# motor_driver_2.net
KiCad netlist of a schematic drawn in Altium Designer
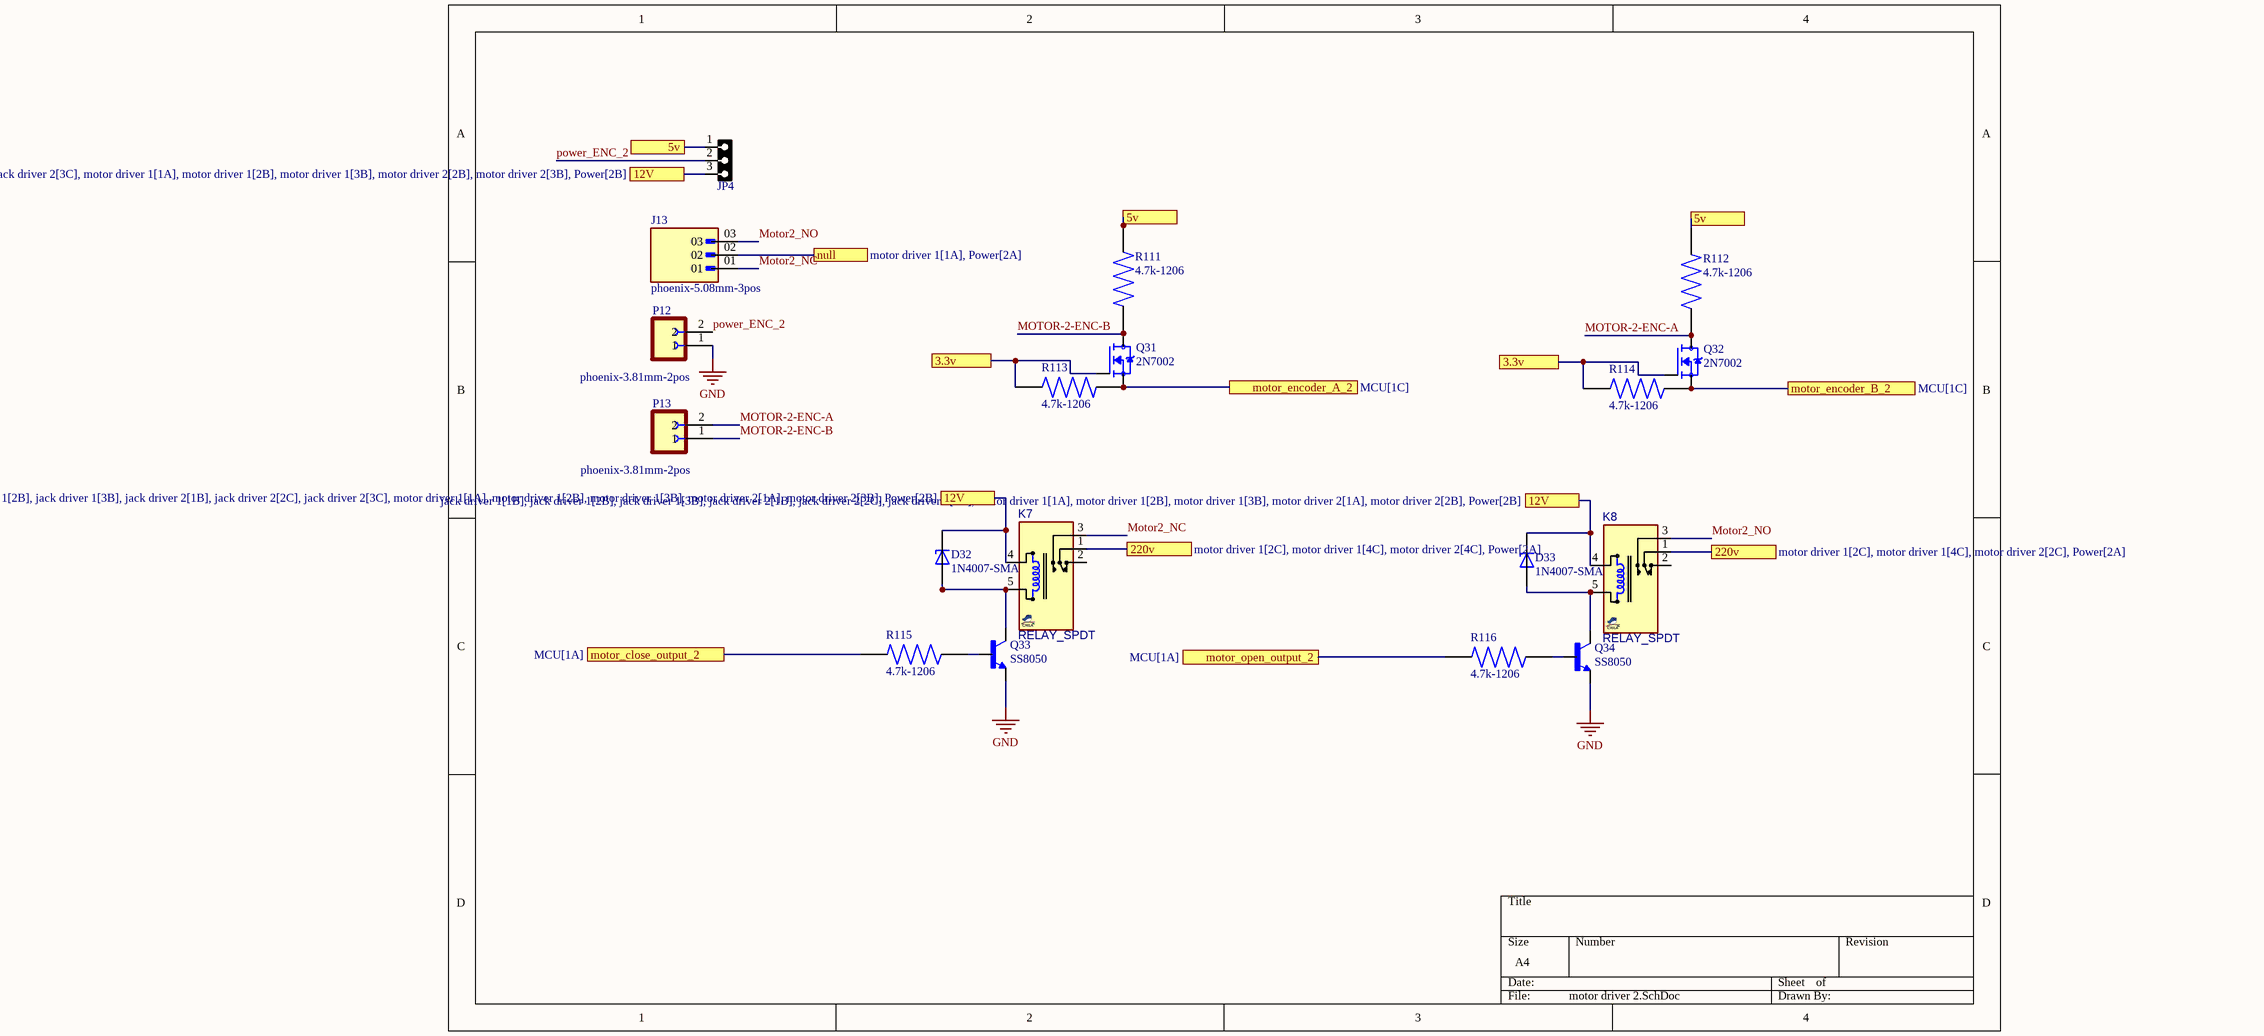
[diagram p0: motor driver 2.SchDoc]

(export (version "E")
  (design (tool "Eeschema 10.0.6"))
  (components
    (comp (ref "D32")
      (value "1N4007-SMA")
      (footprint "DIOM4325X250N")
      (description "400W, 30.4V, 5%, Unidirectional, TVS")
      (fields (field (name "MF") "Taiwan Semiconductor") (field (name "MP") "SMAJ26A"))
      (libsource (lib "diode-sma") (part "SMAJ26A"))
    )
    (comp (ref "D33")
      (value "1N4007-SMA")
      (footprint "DIOM4325X250N")
      (description "400W, 30.4V, 5%, Unidirectional, TVS")
      (fields (field (name "MF") "Taiwan Semiconductor") (field (name "MP") "SMAJ26A"))
      (libsource (lib "diode-sma") (part "SMAJ26A"))
    )
    (comp (ref "J13")
      (value "phoenix-5.08mm-3pos")
      (footprint "PHOENIX_1759020")
      (description "Pluggable Header 5.08mm 12AWG 320V 12A 3 Position COMBICON MSTB Series ¦ Phoenix Contact 1759020")
      (fields (field (name "MF") "Phoenix Contact") (field (name "MP") "1759020"))
      (libsource (lib "phoenix-3pos") (part "1759020"))
    )
    (comp (ref "JP4")
      (value "HDRF3")
      (footprint "HDRLP_F_1X3")
      (description "CONN, HEADER, Male, pitch: 2.54mm, 3POS")
      (libsource (lib "conn_2.54mm_lp") (part "HDRLP_F_1X3"))
    )
    (comp (ref "K7")
      (value "RELAY_SPDT")
      (footprint "REL_SPDT_5_1512")
      (description "Relay, SPDT, 5P, 15.4X12.1mm, 16V/30A")
      (fields (field (name "MANF") "OMRON") (field (name "MANF_P#") "G8QN-1C4 DC12"))
      (libsource (lib "relay") (part "RELAY_SPDT_5_1512_G8QN"))
    )
    (comp (ref "K8")
      (value "RELAY_SPDT")
      (footprint "REL_SPDT_5_1512")
      (description "Relay, SPDT, 5P, 15.4X12.1mm, 16V/30A")
      (fields (field (name "MANF") "OMRON") (field (name "MANF_P#") "G8QN-1C4 DC12"))
      (libsource (lib "relay") (part "RELAY_SPDT_5_1512_G8QN"))
    )
    (comp (ref "P12")
      (value "phoenix-3.81mm-2pos")
      (footprint "PHOENIX_1803578")
      (description "2 Position Terminal Block Plug, Female Sockets 0.150 (3.81mm) 180Â° Free Hanging (In-Line)")
      (fields (field (name "MF") "Phoenix Contact") (field (name "MP") "1803578"))
      (libsource (lib "terminal-phoenix-3.81mm-2pos") (part "1803578"))
    )
    (comp (ref "P13")
      (value "phoenix-3.81mm-2pos")
      (footprint "PHOENIX_1803578")
      (description "2 Position Terminal Block Plug, Female Sockets 0.150 (3.81mm) 180Â° Free Hanging (In-Line)")
      (fields (field (name "MF") "Phoenix Contact") (field (name "MP") "1803578"))
      (libsource (lib "terminal-phoenix-3.81mm-2pos") (part "1803578"))
    )
    (comp (ref "Q31")
      (value "2N7002")
      (footprint "SOT95P240X111-3N")
      (description "N-Channel 60V 280mA (Ta) 350mW (Ta) Surface Mount SOT-23-3 (TO-236)")
      (fields (field (name "MF") "{'manufacturer': u'onsemi'}"))
      (libsource (lib "2N7002-SOT23") (part "2N7002"))
    )
    (comp (ref "Q32")
      (value "2N7002")
      (footprint "SOT95P240X111-3N")
      (description "N-Channel 60V 280mA (Ta) 350mW (Ta) Surface Mount SOT-23-3 (TO-236)")
      (fields (field (name "MF") "{'manufacturer': u'onsemi'}"))
      (libsource (lib "2N7002-SOT23") (part "2N7002"))
    )
    (comp (ref "Q33")
      (value "SS8050")
      (footprint "TRANS_SS8050-G")
      (description "Bipolar (BJT) Transistor NPN 25 V 1.5 A 100MHz 300 mW Surface Mount SOT-23-3")
      (fields (field (name "DIGI-KEY_PART_NUMBER") "641-1790-2-ND") (field (name "MP") "SS8050G"))
      (libsource (lib "SS8050-G") (part "SS8050-G"))
    )
    (comp (ref "Q34")
      (value "SS8050")
      (footprint "TRANS_SS8050-G")
      (description "Bipolar (BJT) Transistor NPN 25 V 1.5 A 100MHz 300 mW Surface Mount SOT-23-3")
      (fields (field (name "DIGI-KEY_PART_NUMBER") "641-1790-2-ND") (field (name "MP") "SS8050G"))
      (libsource (lib "SS8050-G") (part "SS8050-G"))
    )
    (comp (ref "R111")
      (value "4.7k-1206")
      (footprint "RESC3015X65N")
      (description "Res Thin Film 1206 10K Ohm 0.1% 1/8W Â±25ppm/Â°C Molded SMD SMD Paper T/R")
      (fields (field (name "MF") "TE Connectivity") (field (name "MP") "CPF1206B10KE1"))
      (libsource (lib "resistor-1206") (part "CPF1206B10KE1"))
    )
    (comp (ref "R112")
      (value "4.7k-1206")
      (footprint "RESC3015X65N")
      (description "Res Thin Film 1206 10K Ohm 0.1% 1/8W Â±25ppm/Â°C Molded SMD SMD Paper T/R")
      (fields (field (name "MF") "TE Connectivity") (field (name "MP") "CPF1206B10KE1"))
      (libsource (lib "resistor-1206") (part "CPF1206B10KE1"))
    )
    (comp (ref "R113")
      (value "4.7k-1206")
      (footprint "RESC3015X65N")
      (description "Res Thin Film 1206 10K Ohm 0.1% 1/8W Â±25ppm/Â°C Molded SMD SMD Paper T/R")
      (fields (field (name "MF") "TE Connectivity") (field (name "MP") "CPF1206B10KE1"))
      (libsource (lib "resistor-1206") (part "CPF1206B10KE1"))
    )
    (comp (ref "R114")
      (value "4.7k-1206")
      (footprint "RESC3015X65N")
      (description "Res Thin Film 1206 10K Ohm 0.1% 1/8W Â±25ppm/Â°C Molded SMD SMD Paper T/R")
      (fields (field (name "MF") "TE Connectivity") (field (name "MP") "CPF1206B10KE1"))
      (libsource (lib "resistor-1206") (part "CPF1206B10KE1"))
    )
    (comp (ref "R115")
      (value "4.7k-1206")
      (footprint "RESC3015X65N")
      (description "Res Thin Film 1206 10K Ohm 0.1% 1/8W Â±25ppm/Â°C Molded SMD SMD Paper T/R")
      (fields (field (name "MF") "TE Connectivity") (field (name "MP") "CPF1206B10KE1"))
      (libsource (lib "resistor-1206") (part "CPF1206B10KE1"))
    )
    (comp (ref "R116")
      (value "4.7k-1206")
      (footprint "RESC3015X65N")
      (description "Res Thin Film 1206 10K Ohm 0.1% 1/8W Â±25ppm/Â°C Molded SMD SMD Paper T/R")
      (fields (field (name "MF") "TE Connectivity") (field (name "MP") "CPF1206B10KE1"))
      (libsource (lib "resistor-1206") (part "CPF1206B10KE1"))
    )
  )
  (nets
    (net (code "1") (name "/3.3v") (class "Default")
      (node (ref "Q31") (pin "1") (pinfunction "G_1") (pintype "passive"))
      (node (ref "Q32") (pin "1") (pinfunction "G_1") (pintype "passive"))
      (node (ref "R113") (pin "2") (pinfunction "2_2") (pintype "passive"))
      (node (ref "R114") (pin "2") (pinfunction "2_2") (pintype "passive"))
    )
    (net (code "2") (name "/5v") (class "Default")
      (node (ref "JP4") (pin "1") (pinfunction "1_1") (pintype "passive"))
      (node (ref "R111") (pin "2") (pinfunction "2_2") (pintype "passive"))
      (node (ref "R112") (pin "2") (pinfunction "2_2") (pintype "passive"))
    )
    (net (code "3") (name "/12V") (class "Default")
      (node (ref "D32") (pin "C") (pinfunction "C_C") (pintype "passive"))
      (node (ref "D33") (pin "C") (pinfunction "C_C") (pintype "passive"))
      (node (ref "JP4") (pin "3") (pinfunction "3_3") (pintype "passive"))
      (node (ref "K7") (pin "4") (pinfunction "T1_4") (pintype "passive"))
      (node (ref "K8") (pin "4") (pinfunction "T1_4") (pintype "passive"))
    )
    (net (code "4") (name "/220v") (class "Default")
      (node (ref "K7") (pin "1") (pinfunction "COM_1") (pintype "passive"))
      (node (ref "K8") (pin "1") (pinfunction "COM_1") (pintype "passive"))
    )
    (net (code "5") (name "/MOTOR-2-ENC-A") (class "Default")
      (node (ref "P13") (pin "2") (pinfunction "2_2") (pintype "passive"))
      (node (ref "Q32") (pin "3") (pinfunction "D_3") (pintype "passive"))
      (node (ref "R112") (pin "1") (pinfunction "1_1") (pintype "passive"))
    )
    (net (code "6") (name "/MOTOR-2-ENC-B") (class "Default")
      (node (ref "P13") (pin "1") (pinfunction "1_1") (pintype "passive"))
      (node (ref "Q31") (pin "3") (pinfunction "D_3") (pintype "passive"))
      (node (ref "R111") (pin "1") (pinfunction "1_1") (pintype "passive"))
    )
    (net (code "7") (name "/Motor2_NC") (class "Default")
      (node (ref "J13") (pin "01") (pinfunction "01_01") (pintype "passive"))
      (node (ref "K7") (pin "3") (pinfunction "NO_3") (pintype "passive"))
    )
    (net (code "8") (name "/Motor2_NO") (class "Default")
      (node (ref "J13") (pin "03") (pinfunction "03_03") (pintype "passive"))
      (node (ref "K8") (pin "3") (pinfunction "NO_3") (pintype "passive"))
    )
    (net (code "9") (name "/motor_close_output_2") (class "Default")
      (node (ref "R115") (pin "2") (pinfunction "2_2") (pintype "passive"))
    )
    (net (code "10") (name "/motor_encoder_A_2") (class "Default")
      (node (ref "Q31") (pin "2") (pinfunction "S_2") (pintype "passive"))
      (node (ref "R113") (pin "1") (pinfunction "1_1") (pintype "passive"))
    )
    (net (code "11") (name "/motor_encoder_B_2") (class "Default")
      (node (ref "Q32") (pin "2") (pinfunction "S_2") (pintype "passive"))
      (node (ref "R114") (pin "1") (pinfunction "1_1") (pintype "passive"))
    )
    (net (code "12") (name "/motor_open_output_2") (class "Default")
      (node (ref "R116") (pin "2") (pinfunction "2_2") (pintype "passive"))
    )
    (net (code "13") (name "/null") (class "Default")
      (node (ref "J13") (pin "02") (pinfunction "02_02") (pintype "passive"))
    )
    (net (code "14") (name "/power_ENC_2") (class "Default")
      (node (ref "JP4") (pin "2") (pinfunction "2_2") (pintype "passive"))
      (node (ref "P12") (pin "2") (pinfunction "2_2") (pintype "passive"))
    )
    (net (code "15") (name "GND") (class "Default")
      (node (ref "P12") (pin "1") (pinfunction "1_1") (pintype "passive"))
      (node (ref "Q33") (pin "2") (pinfunction "E_2") (pintype "passive"))
      (node (ref "Q34") (pin "2") (pinfunction "E_2") (pintype "passive"))
    )
    (net (code "16") (name "Net-(K7-T2)") (class "Default")
      (node (ref "D32") (pin "A") (pinfunction "A_A") (pintype "passive"))
      (node (ref "K7") (pin "5") (pinfunction "T2_5") (pintype "passive"))
      (node (ref "Q33") (pin "3") (pinfunction "C_3") (pintype "passive"))
    )
    (net (code "17") (name "Net-(K8-T2)") (class "Default")
      (node (ref "D33") (pin "A") (pinfunction "A_A") (pintype "passive"))
      (node (ref "K8") (pin "5") (pinfunction "T2_5") (pintype "passive"))
      (node (ref "Q34") (pin "3") (pinfunction "C_3") (pintype "passive"))
    )
    (net (code "18") (name "Net-(Q33-B)") (class "Default")
      (node (ref "Q33") (pin "1") (pinfunction "B_1") (pintype "passive"))
      (node (ref "R115") (pin "1") (pinfunction "1_1") (pintype "passive"))
    )
    (net (code "19") (name "Net-(Q34-B)") (class "Default")
      (node (ref "Q34") (pin "1") (pinfunction "B_1") (pintype "passive"))
      (node (ref "R116") (pin "1") (pinfunction "1_1") (pintype "passive"))
    )
    (net (code "20") (name "unconnected-(K7-NC-Pad2)") (class "Default")
      (node (ref "K7") (pin "2") (pinfunction "NC_2") (pintype "passive"))
    )
    (net (code "21") (name "unconnected-(K8-NC-Pad2)") (class "Default")
      (node (ref "K8") (pin "2") (pinfunction "NC_2") (pintype "passive"))
    )
  )
)
